# ZIGBEE.net
KiCad netlist of a schematic drawn in Altium Designer
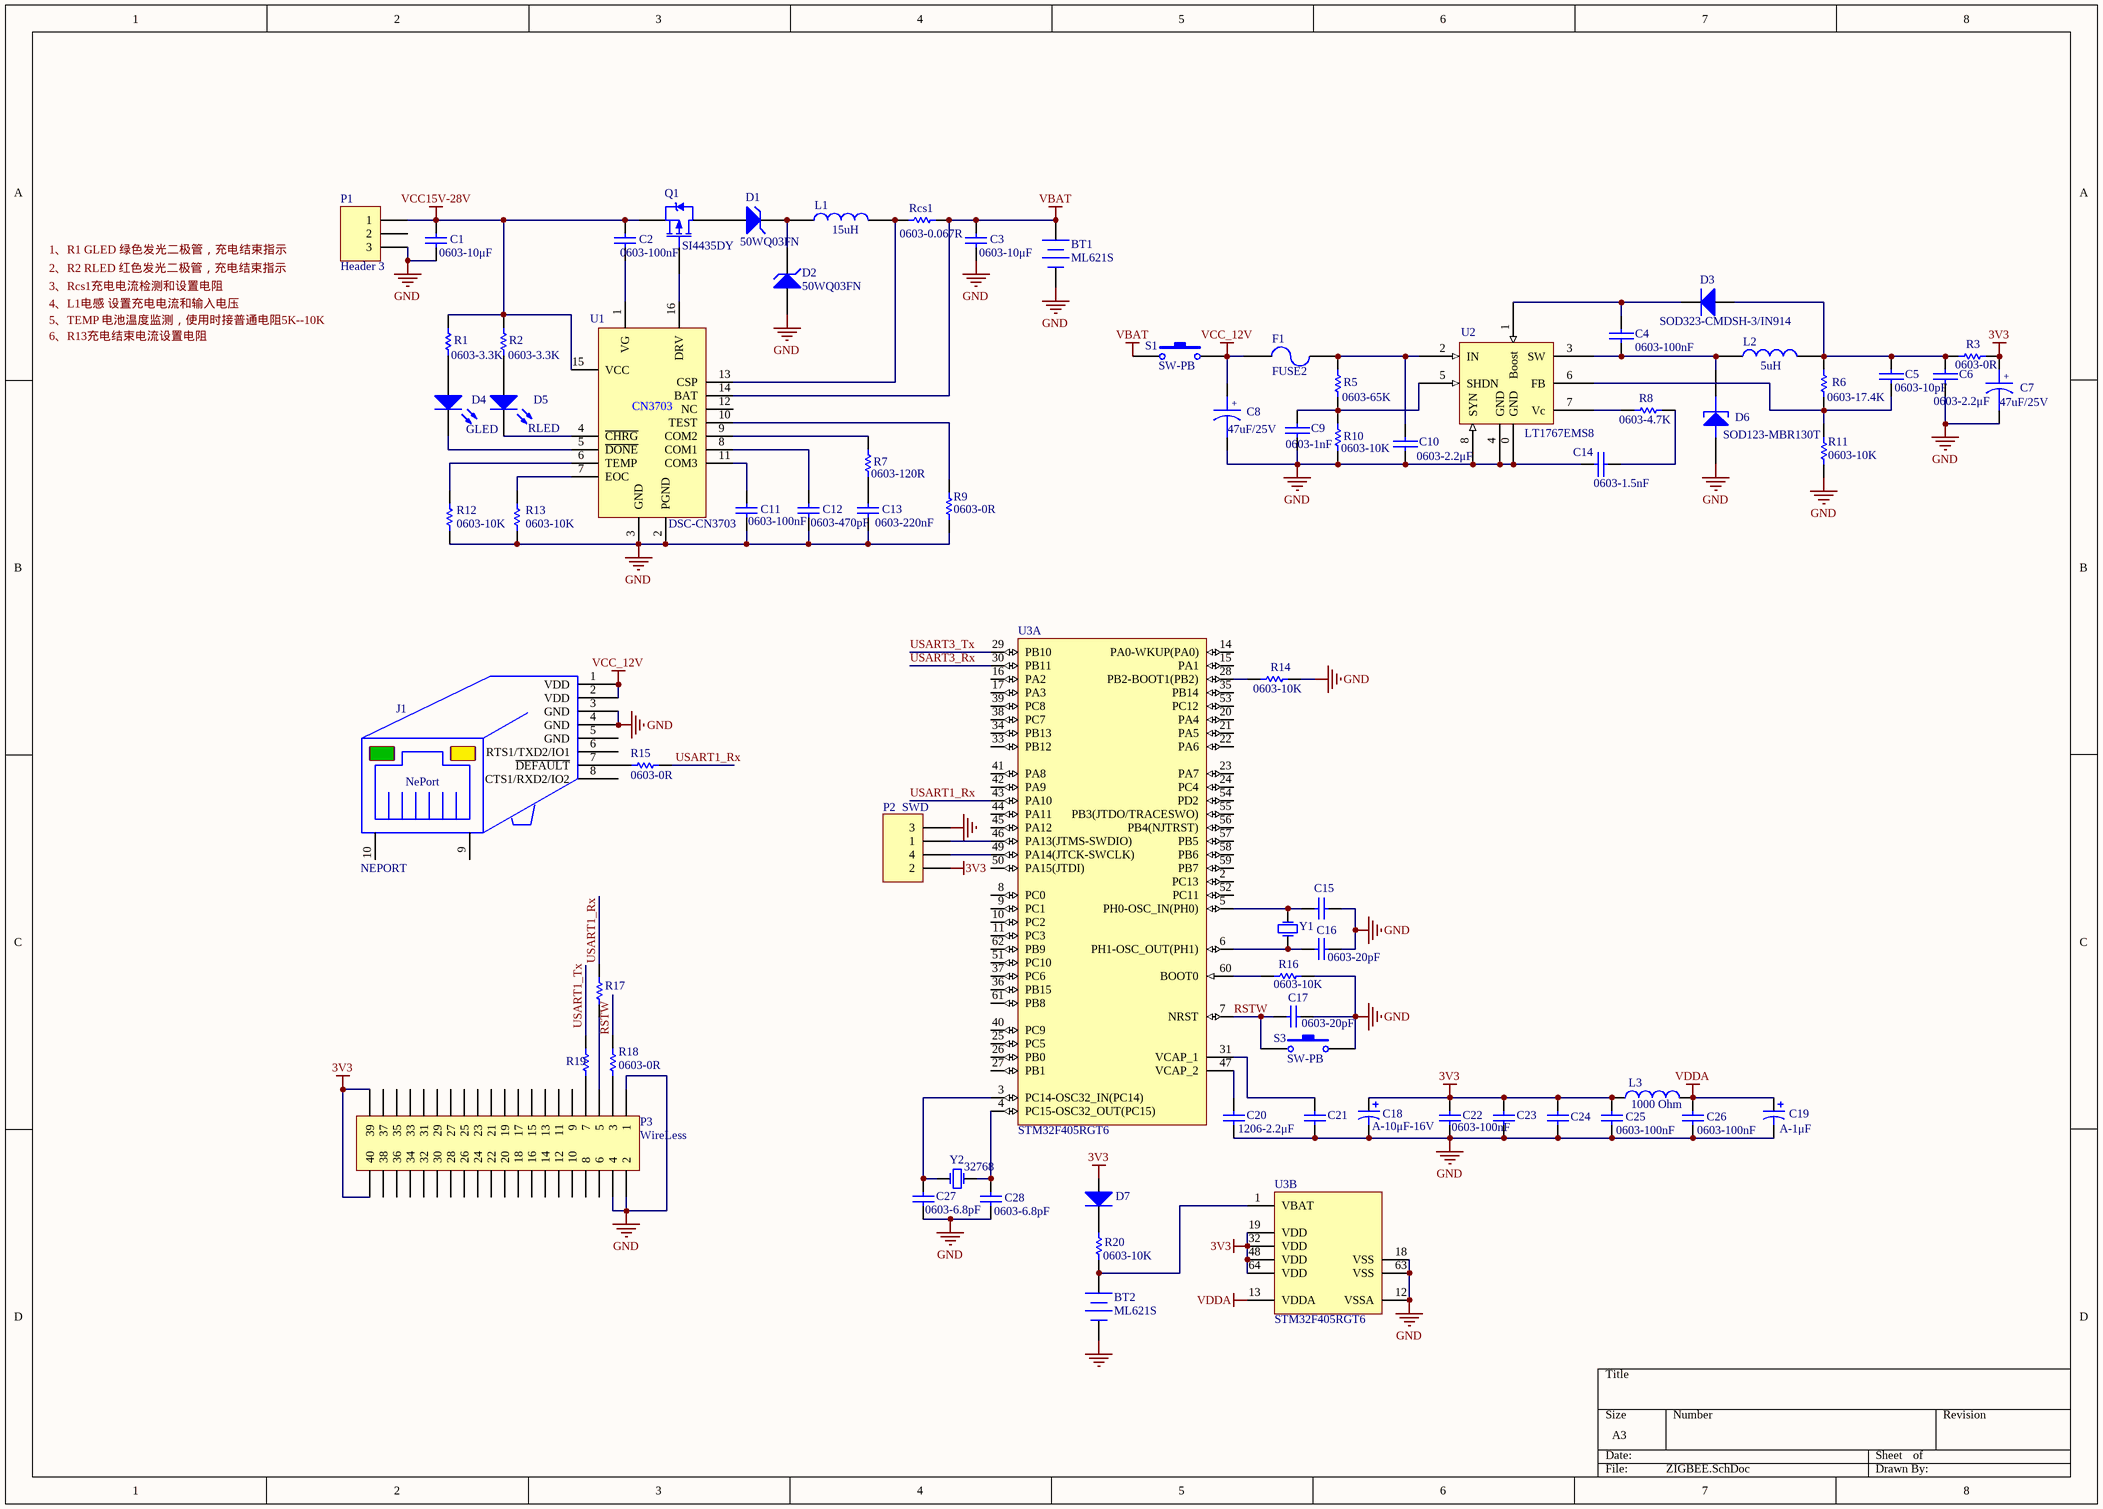
[diagram p0: ZIGBEE.SchDoc]

(export (version "E")
  (design (tool "Eeschema 10.0.6"))
  (components
    (comp (ref "BT1")
      (value "ML621S")
      (footprint "TJC3-2A")
      (description "Multicell Battery")
      (fields (field (name "PUBLISHER") "Altium Limited"))
      (libsource (lib "Miscellaneous Devices") (part "Battery"))
    )
    (comp (ref "BT2")
      (value "ML621S")
      (footprint "ML621")
      (description "Multicell Battery")
      (fields (field (name "PUBLISHER") "Altium Limited"))
      (libsource (lib "Miscellaneous Devices") (part "Battery"))
    )
    (comp (ref "C1")
      (value "0603-10μF")
      (footprint "0603C")
      (description "Capacitor")
      (fields (field (name "PUBLISHER") "Altium Limited"))
      (libsource (lib "Miscellaneous Devices") (part "Cap"))
    )
    (comp (ref "C2")
      (value "0603-100nF")
      (footprint "0603C")
      (description "Capacitor")
      (fields (field (name "PUBLISHER") "Altium Limited"))
      (libsource (lib "Miscellaneous Devices") (part "Cap"))
    )
    (comp (ref "C3")
      (value "0603-10μF")
      (footprint "0603C")
      (description "Capacitor")
      (fields (field (name "PUBLISHER") "Altium Limited"))
      (libsource (lib "Miscellaneous Devices") (part "Cap"))
    )
    (comp (ref "C4")
      (value "0603-100nF")
      (footprint "0603C")
      (description "Capacitor")
      (libsource (lib "采集器") (part "普通电容"))
    )
    (comp (ref "C5")
      (value "0603-10pF")
      (footprint "0603C")
      (description "Capacitor")
      (libsource (lib "采集器") (part "普通电容"))
    )
    (comp (ref "C6")
      (value "0603-2.2μF")
      (footprint "0603C")
      (description "Capacitor")
      (libsource (lib "采集器") (part "普通电容"))
    )
    (comp (ref "C7")
      (value "47uF/25V")
      (footprint "SMD-47uF/25V")
      (description "Capacitor")
      (libsource (lib "采集器") (part "电解电容"))
    )
    (comp (ref "C8")
      (value "47uF/25V")
      (footprint "SMD-47uF/25V")
      (description "Capacitor")
      (libsource (lib "采集器") (part "电解电容"))
    )
    (comp (ref "C9")
      (value "0603-1nF")
      (footprint "0603C")
      (description "Capacitor")
      (libsource (lib "采集器") (part "普通电容"))
    )
    (comp (ref "C10")
      (value "0603-2.2μF")
      (footprint "0603C")
      (description "Capacitor")
      (libsource (lib "采集器") (part "普通电容"))
    )
    (comp (ref "C11")
      (value "0603-100nF")
      (footprint "0603C")
      (description "Capacitor")
      (fields (field (name "PUBLISHER") "Altium Limited"))
      (libsource (lib "Miscellaneous Devices") (part "Cap"))
    )
    (comp (ref "C12")
      (value "0603-470pF")
      (footprint "0603C")
      (description "Capacitor")
      (fields (field (name "PUBLISHER") "Altium Limited"))
      (libsource (lib "Miscellaneous Devices") (part "Cap"))
    )
    (comp (ref "C13")
      (value "0603-220nF")
      (footprint "0603C")
      (description "Capacitor")
      (fields (field (name "PUBLISHER") "Altium Limited"))
      (libsource (lib "Miscellaneous Devices") (part "Cap"))
    )
    (comp (ref "C14")
      (value "0603-1.5nF")
      (footprint "0603C")
      (description "Capacitor")
      (libsource (lib "采集器") (part "普通电容"))
    )
    (comp (ref "C15")
      (value "0603-20pF")
      (footprint "0603C")
      (description "Capacitor")
      (fields (field (name "PUBLISHER") "Altium Limited"))
      (libsource (lib "Miscellaneous Devices") (part "Cap"))
    )
    (comp (ref "C16")
      (value "0603-20pF")
      (footprint "0603C")
      (description "Capacitor")
      (fields (field (name "PUBLISHER") "Altium Limited"))
      (libsource (lib "Miscellaneous Devices") (part "Cap"))
    )
    (comp (ref "C17")
      (value "0603-20pF")
      (footprint "0603C")
      (description "Capacitor")
      (fields (field (name "PUBLISHER") "Altium Limited"))
      (libsource (lib "Miscellaneous Devices") (part "Cap"))
    )
    (comp (ref "C18")
      (value "A-10μF-16V")
      (footprint "TANA")
      (description "Polarized Capacitor (Radial)")
      (fields (field (name "PUBLISHER") "Altium Limited"))
      (libsource (lib "Miscellaneous Devices") (part "Cap Pol1"))
    )
    (comp (ref "C19")
      (value "A-1μF")
      (footprint "TANA")
      (description "Polarized Capacitor (Radial)")
      (fields (field (name "PUBLISHER") "Altium Limited"))
      (libsource (lib "Miscellaneous Devices") (part "Cap Pol1"))
    )
    (comp (ref "C20")
      (value "1206-2.2μF")
      (description "Capacitor")
      (fields (field (name "PUBLISHER") "Altium Limited"))
      (libsource (lib "Miscellaneous Devices") (part "Cap"))
    )
    (comp (ref "C21")
      (value "1206-2.2μF")
      (description "Capacitor")
      (fields (field (name "PUBLISHER") "Altium Limited"))
      (libsource (lib "Miscellaneous Devices") (part "Cap"))
    )
    (comp (ref "C22")
      (value "0603-100nF")
      (footprint "0603C")
      (description "Capacitor")
      (fields (field (name "PUBLISHER") "Altium Limited"))
      (libsource (lib "Miscellaneous Devices") (part "Cap"))
    )
    (comp (ref "C23")
      (value "0603-100nF")
      (footprint "0603C")
      (description "Capacitor")
      (fields (field (name "PUBLISHER") "Altium Limited"))
      (libsource (lib "Miscellaneous Devices") (part "Cap"))
    )
    (comp (ref "C24")
      (value "0603-100nF")
      (footprint "0603C")
      (description "Capacitor")
      (fields (field (name "PUBLISHER") "Altium Limited"))
      (libsource (lib "Miscellaneous Devices") (part "Cap"))
    )
    (comp (ref "C25")
      (value "0603-100nF")
      (footprint "0603C")
      (description "Capacitor")
      (fields (field (name "PUBLISHER") "Altium Limited"))
      (libsource (lib "Miscellaneous Devices") (part "Cap"))
    )
    (comp (ref "C26")
      (value "0603-100nF")
      (footprint "0603C")
      (description "Capacitor")
      (fields (field (name "PUBLISHER") "Altium Limited"))
      (libsource (lib "Miscellaneous Devices") (part "Cap"))
    )
    (comp (ref "C27")
      (value "0603-6.8pF")
      (footprint "0603C")
      (description "Capacitor")
      (fields (field (name "PUBLISHER") "Altium Limited"))
      (libsource (lib "Miscellaneous Devices") (part "Cap"))
    )
    (comp (ref "C28")
      (value "0603-6.8pF")
      (footprint "0603C")
      (description "Capacitor")
      (fields (field (name "PUBLISHER") "Altium Limited"))
      (libsource (lib "Miscellaneous Devices") (part "Cap"))
    )
    (comp (ref "D1")
      (value "50WQ03FN")
      (footprint "DO-214AC")
      (description "Zener Diode")
      (fields (field (name "PUBLISHER") "Altium Limited"))
      (libsource (lib "Miscellaneous Devices") (part "D Zener"))
    )
    (comp (ref "D2")
      (value "50WQ03FN")
      (footprint "DO-214AC")
      (description "Zener Diode")
      (fields (field (name "PUBLISHER") "Altium Limited"))
      (libsource (lib "Miscellaneous Devices") (part "D Zener"))
    )
    (comp (ref "D3")
      (value "SOD323-CMDSH-3/IN914")
      (footprint "SOD-323")
      (libsource (lib "采集器") (part "DIODE"))
    )
    (comp (ref "D4")
      (value "GLED")
      (footprint "0603D")
      (description "Typical INFRARED GaAs LED")
      (fields (field (name "PUBLISHER") "Altium Limited"))
      (libsource (lib "Miscellaneous Devices") (part "LED0"))
    )
    (comp (ref "D5")
      (value "RLED")
      (footprint "0603D")
      (description "Typical INFRARED GaAs LED")
      (fields (field (name "PUBLISHER") "Altium Limited"))
      (libsource (lib "Miscellaneous Devices") (part "LED0"))
    )
    (comp (ref "D6")
      (value "SOD123-MBR130T")
      (footprint "SOD123/X.85")
      (description "Tunnel FDiode")
      (libsource (lib "采集器") (part "TUNNEL"))
    )
    (comp (ref "D7")
      (value "1N4148")
      (footprint "SOD-80/MLL34")
      (description "High Conductance Fast Diode")
      (fields (field (name "PUBLISHER") "Altium Limited"))
      (libsource (lib "Miscellaneous Devices") (part "Diode 1N4148"))
    )
    (comp (ref "F1")
      (value "FUSE2")
      (footprint "0603")
      (description "Fuse")
      (libsource (lib "采集器") (part "FUSE2"))
    )
    (comp (ref "J1")
      (value "NEPORT")
      (footprint "RJ45_8P8C")
      (description "serial to ethernet RJ45 jack")
      (libsource (lib "Neport") (part "NEPORT"))
    )
    (comp (ref "L1") (value "15uH") (footprint "SMD") (libsource (lib "采集器") (part "INDUCTOR")))
    (comp (ref "L2") (value "5uH") (footprint "SMD") (libsource (lib "采集器") (part "INDUCTOR")))
    (comp (ref "L3")
      (value "1000 Ohm")
      (footprint "INDC4516AM")
      (description "BLM41PG102SN1L\\CBW451616U900")
      (fields (field (name "PUBLISHER") "Altium Limited"))
      (libsource (lib "Miscellaneous Devices") (part "Inductor"))
    )
    (comp (ref "P1")
      (value "Header 3")
      (footprint "XH-2.54-3")
      (description "Header, 3-Pin")
      (fields (field (name "PUBLISHER") "Altium Limited"))
      (libsource (lib "Miscellaneous Connectors") (part "Header 3"))
    )
    (comp (ref "P2")
      (value "SWD")
      (footprint "HDR1X4")
      (description "Header, 4-Pin")
      (fields (field (name "PUBLISHER") "Altium Limited"))
      (libsource (lib "Miscellaneous Connectors") (part "Header 4"))
    )
    (comp (ref "P3")
      (value "WireLess")
      (footprint "SMALL/MIDDLE OEM MODEM")
      (description "Header, 20-Pin, Dual row")
      (fields (field (name "PUBLISHER") "Altium Limited"))
      (libsource (lib "Miscellaneous Connectors") (part "Header 20X2"))
    )
    (comp (ref "Q1")
      (value "SI4435DY")
      (footprint "TO-220AB")
      (description "P-Channel Power MOSFET")
      (fields (field (name "PUBLISHER") "Altium Limited"))
      (libsource (lib "Miscellaneous Devices") (part "PMOS-2"))
    )
    (comp (ref "R1")
      (value "0603-3.3K")
      (footprint "0603")
      (description "Resistor")
      (fields (field (name "PUBLISHER") "Altium Limited"))
      (libsource (lib "Miscellaneous Devices") (part "Res1"))
    )
    (comp (ref "R2")
      (value "0603-3.3K")
      (footprint "0603")
      (description "Resistor")
      (fields (field (name "PUBLISHER") "Altium Limited"))
      (libsource (lib "Miscellaneous Devices") (part "Res1"))
    )
    (comp (ref "R3")
      (value "0603-0R")
      (footprint "0603")
      (description "Resistor")
      (fields (field (name "PUBLISHER") "Altium Limited"))
      (libsource (lib "Miscellaneous Devices") (part "Res1"))
    )
    (comp (ref "R5")
      (value "0603-65K")
      (footprint "0603")
      (description "Resistor")
      (fields (field (name "PUBLISHER") "Altium Limited"))
      (libsource (lib "Miscellaneous Devices") (part "Res1"))
    )
    (comp (ref "R6")
      (value "0603-17.4K")
      (footprint "0603")
      (description "Resistor")
      (fields (field (name "PUBLISHER") "Altium Limited"))
      (libsource (lib "Miscellaneous Devices") (part "Res1"))
    )
    (comp (ref "R7")
      (value "0603-120R")
      (footprint "0603")
      (description "Resistor")
      (fields (field (name "PUBLISHER") "Altium Limited"))
      (libsource (lib "Miscellaneous Devices") (part "Res1"))
    )
    (comp (ref "R8")
      (value "0603-4.7K")
      (footprint "0603")
      (description "Resistor")
      (fields (field (name "PUBLISHER") "Altium Limited"))
      (libsource (lib "Miscellaneous Devices") (part "Res1"))
    )
    (comp (ref "R9")
      (value "0603-0R")
      (footprint "0603")
      (description "Resistor")
      (fields (field (name "PUBLISHER") "Altium Limited"))
      (libsource (lib "Miscellaneous Devices") (part "Res1"))
    )
    (comp (ref "R10")
      (value "0603-10K")
      (footprint "0603")
      (description "Resistor")
      (fields (field (name "PUBLISHER") "Altium Limited"))
      (libsource (lib "Miscellaneous Devices") (part "Res1"))
    )
    (comp (ref "R11")
      (value "0603-10K")
      (footprint "0603")
      (description "Resistor")
      (fields (field (name "PUBLISHER") "Altium Limited"))
      (libsource (lib "Miscellaneous Devices") (part "Res1"))
    )
    (comp (ref "R12")
      (value "0603-10K")
      (footprint "0603")
      (description "Resistor")
      (fields (field (name "PUBLISHER") "Altium Limited"))
      (libsource (lib "Miscellaneous Devices") (part "Res1"))
    )
    (comp (ref "R13")
      (value "0603-10K")
      (footprint "0603")
      (description "Resistor")
      (fields (field (name "PUBLISHER") "Altium Limited"))
      (libsource (lib "Miscellaneous Devices") (part "Res1"))
    )
    (comp (ref "R14")
      (value "0603-10K")
      (footprint "0603")
      (description "Resistor")
      (fields (field (name "PUBLISHER") "Altium Limited"))
      (libsource (lib "Miscellaneous Devices") (part "Res1"))
    )
    (comp (ref "R15")
      (value "0603-0R")
      (footprint "0603")
      (description "Resistor")
      (fields (field (name "PUBLISHER") "Altium Limited"))
      (libsource (lib "Miscellaneous Devices") (part "Res1"))
    )
    (comp (ref "R16")
      (value "0603-10K")
      (footprint "0603")
      (description "Resistor")
      (fields (field (name "PUBLISHER") "Altium Limited"))
      (libsource (lib "Miscellaneous Devices") (part "Res1"))
    )
    (comp (ref "R17")
      (value "0603-0R")
      (footprint "0603")
      (description "Resistor")
      (fields (field (name "PUBLISHER") "Altium Limited"))
      (libsource (lib "Miscellaneous Devices") (part "Res1"))
    )
    (comp (ref "R18")
      (value "0603-0R")
      (footprint "0603")
      (description "Resistor")
      (fields (field (name "PUBLISHER") "Altium Limited"))
      (libsource (lib "Miscellaneous Devices") (part "Res1"))
    )
    (comp (ref "R19")
      (value "0603-0R")
      (footprint "0603")
      (description "Resistor")
      (fields (field (name "PUBLISHER") "Altium Limited"))
      (libsource (lib "Miscellaneous Devices") (part "Res1"))
    )
    (comp (ref "R20")
      (value "0603-10K")
      (footprint "0603")
      (description "Resistor")
      (fields (field (name "PUBLISHER") "Altium Limited"))
      (libsource (lib "Miscellaneous Devices") (part "Res1"))
    )
    (comp (ref "Rcs1")
      (value "0603-0.067R")
      (footprint "0603")
      (description "Resistor")
      (fields (field (name "PUBLISHER") "Altium Limited"))
      (libsource (lib "Miscellaneous Devices") (part "Res1"))
    )
    (comp (ref "S1")
      (value "SW-PB")
      (footprint "TJC3-2A")
      (description "Switch")
      (fields (field (name "PUBLISHER") "Altium Limited"))
      (libsource (lib "Miscellaneous Devices") (part "SW-PB"))
    )
    (comp (ref "S3")
      (value "SW-PB")
      (footprint "SW3*4*2MM")
      (description "Switch")
      (fields (field (name "PUBLISHER") "Altium Limited"))
      (libsource (lib "Miscellaneous Devices") (part "SW-PB"))
    )
    (comp (ref "U1") (value "DSC-CN3703") (footprint "TSSOP16") (libsource (lib "SCHKU") (part "DSC-CN3703")))
    (comp (ref "U2") (value "LT1767EMS8") (footprint "MS8_N") (libsource (lib "采集器") (part "LT1767EMS8")))
    (comp (ref "U3")
      (value "STM32F405RGT6")
      (footprint "TQFP64_M")
      (fields (field (name "MANUFACTURER") "STMicroelectronics"))
      (libsource (lib "") (part "STM32F405RGT6_1"))
    )
    (comp (ref "Y1")
      (value "8MHz")
      (footprint "XTAL")
      (description "Crystal Oscillator")
      (fields (field (name "PUBLISHER") "Altium Limited"))
      (libsource (lib "Miscellaneous Devices") (part "XTAL"))
    )
    (comp (ref "Y2")
      (value "32768")
      (footprint "1206CY")
      (description "Crystal Oscillator")
      (fields (field (name "PUBLISHER") "Altium Limited"))
      (libsource (lib "Miscellaneous Devices") (part "XTAL"))
    )
  )
  (nets
    (net (code "7") (name "/RSTW") (class "Default")
      (node (ref "C17") (pin "2") (pinfunction "2_2") (pintype "passive"))
      (node (ref "R18") (pin "1") (pinfunction "1_1") (pintype "passive"))
      (node (ref "S3") (pin "1") (pinfunction "1_1") (pintype "passive"))
      (node (ref "U3") (pin "7") (pinfunction "NRST_7") (pintype "bidirectional"))
    )
    (net (code "8") (name "/USART1_Rx") (class "Default")
      (node (ref "R15") (pin "1") (pinfunction "1_1") (pintype "passive"))
      (node (ref "R17") (pin "1") (pinfunction "1_1") (pintype "passive"))
      (node (ref "U3") (pin "43") (pinfunction "PA10_43") (pintype "bidirectional"))
    )
    (net (code "9") (name "/USART1_Tx") (class "Default")
      (node (ref "R19") (pin "1") (pinfunction "1_1") (pintype "passive"))
    )
    (net (code "10") (name "/USART3_Rx") (class "Default")
      (node (ref "U3") (pin "30") (pinfunction "PB11_30") (pintype "bidirectional"))
    )
    (net (code "11") (name "/USART3_Tx") (class "Default")
      (node (ref "U3") (pin "29") (pinfunction "PB10_29") (pintype "bidirectional"))
    )
    (net (code "12") (name "3V3") (class "Default")
      (node (ref "C18") (pin "1") (pinfunction "1_1") (pintype "passive"))
      (node (ref "C22") (pin "2") (pinfunction "2_2") (pintype "passive"))
      (node (ref "C23") (pin "2") (pinfunction "2_2") (pintype "passive"))
      (node (ref "C24") (pin "2") (pinfunction "2_2") (pintype "passive"))
      (node (ref "C25") (pin "2") (pinfunction "2_2") (pintype "passive"))
      (node (ref "C7") (pin "1") (pinfunction "1_1") (pintype "passive"))
      (node (ref "D7") (pin "1") (pinfunction "A_1") (pintype "passive"))
      (node (ref "L3") (pin "1") (pinfunction "1_1") (pintype "passive"))
      (node (ref "P2") (pin "2") (pinfunction "2_2") (pintype "passive"))
      (node (ref "P3") (pin "39") (pinfunction "39_39") (pintype "passive"))
      (node (ref "P3") (pin "40") (pinfunction "40_40") (pintype "passive"))
      (node (ref "R3") (pin "2") (pinfunction "2_2") (pintype "passive"))
      (node (ref "U3") (pin "19") (pinfunction "VDD_19") (pintype "power_in"))
      (node (ref "U3") (pin "32") (pinfunction "VDD_32") (pintype "power_in"))
      (node (ref "U3") (pin "48") (pinfunction "VDD_48") (pintype "power_in"))
      (node (ref "U3") (pin "64") (pinfunction "VDD_64") (pintype "power_in"))
    )
    (net (code "13") (name "GND") (class "Default")
      (node (ref "BT1") (pin "1") (pinfunction "-_1") (pintype "passive"))
      (node (ref "BT2") (pin "1") (pinfunction "-_1") (pintype "passive"))
      (node (ref "C1") (pin "2") (pinfunction "2_2") (pintype "passive"))
      (node (ref "C10") (pin "2") (pinfunction "2_2") (pintype "passive"))
      (node (ref "C11") (pin "2") (pinfunction "2_2") (pintype "passive"))
      (node (ref "C12") (pin "2") (pinfunction "2_2") (pintype "passive"))
      (node (ref "C13") (pin "2") (pinfunction "2_2") (pintype "passive"))
      (node (ref "C14") (pin "1") (pinfunction "1_1") (pintype "passive"))
      (node (ref "C15") (pin "1") (pinfunction "1_1") (pintype "passive"))
      (node (ref "C16") (pin "1") (pinfunction "1_1") (pintype "passive"))
      (node (ref "C17") (pin "1") (pinfunction "1_1") (pintype "passive"))
      (node (ref "C18") (pin "2") (pinfunction "2_2") (pintype "passive"))
      (node (ref "C19") (pin "2") (pinfunction "2_2") (pintype "passive"))
      (node (ref "C20") (pin "1") (pinfunction "1_1") (pintype "passive"))
      (node (ref "C21") (pin "1") (pinfunction "1_1") (pintype "passive"))
      (node (ref "C22") (pin "1") (pinfunction "1_1") (pintype "passive"))
      (node (ref "C23") (pin "1") (pinfunction "1_1") (pintype "passive"))
      (node (ref "C24") (pin "1") (pinfunction "1_1") (pintype "passive"))
      (node (ref "C25") (pin "1") (pinfunction "1_1") (pintype "passive"))
      (node (ref "C26") (pin "1") (pinfunction "1_1") (pintype "passive"))
      (node (ref "C27") (pin "2") (pinfunction "2_2") (pintype "passive"))
      (node (ref "C28") (pin "2") (pinfunction "2_2") (pintype "passive"))
      (node (ref "C3") (pin "2") (pinfunction "2_2") (pintype "passive"))
      (node (ref "C6") (pin "2") (pinfunction "2_2") (pintype "passive"))
      (node (ref "C7") (pin "2") (pinfunction "2_2") (pintype "passive"))
      (node (ref "C8") (pin "2") (pinfunction "2_2") (pintype "passive"))
      (node (ref "C9") (pin "2") (pinfunction "2_2") (pintype "passive"))
      (node (ref "D2") (pin "1") (pinfunction "A_1") (pintype "passive"))
      (node (ref "D6") (pin "1") (pinfunction "A_1") (pintype "passive"))
      (node (ref "J1") (pin "3") (pinfunction "GND_3") (pintype "passive"))
      (node (ref "J1") (pin "4") (pinfunction "GND_4") (pintype "passive"))
      (node (ref "P1") (pin "3") (pinfunction "3_3") (pintype "passive"))
      (node (ref "P2") (pin "3") (pinfunction "3_3") (pintype "passive"))
      (node (ref "P3") (pin "1") (pinfunction "1_1") (pintype "passive"))
      (node (ref "P3") (pin "2") (pinfunction "2_2") (pintype "passive"))
      (node (ref "P3") (pin "4") (pinfunction "4_4") (pintype "passive"))
      (node (ref "R10") (pin "1") (pinfunction "1_1") (pintype "passive"))
      (node (ref "R11") (pin "1") (pinfunction "1_1") (pintype "passive"))
      (node (ref "R12") (pin "2") (pinfunction "2_2") (pintype "passive"))
      (node (ref "R13") (pin "2") (pinfunction "2_2") (pintype "passive"))
      (node (ref "R14") (pin "2") (pinfunction "2_2") (pintype "passive"))
      (node (ref "R16") (pin "2") (pinfunction "2_2") (pintype "passive"))
      (node (ref "R9") (pin "2") (pinfunction "2_2") (pintype "passive"))
      (node (ref "S3") (pin "2") (pinfunction "2_2") (pintype "passive"))
      (node (ref "U1") (pin "2") (pinfunction "PGND_2") (pintype "passive"))
      (node (ref "U1") (pin "3") (pinfunction "GND_3") (pintype "passive"))
      (node (ref "U2") (pin "0") (pinfunction "GND_0") (pintype "passive"))
      (node (ref "U2") (pin "4") (pinfunction "GND_4") (pintype "passive"))
      (node (ref "U2") (pin "8") (pinfunction "SYN_8") (pintype "input"))
      (node (ref "U3") (pin "12") (pinfunction "VSSA_12") (pintype "power_in"))
      (node (ref "U3") (pin "18") (pinfunction "VSS_18") (pintype "power_in"))
      (node (ref "U3") (pin "63") (pinfunction "VSS_63") (pintype "power_in"))
    )
    (net (code "14") (name "Net-(BT2-+)") (class "Default")
      (node (ref "BT2") (pin "2") (pinfunction "+_2") (pintype "passive"))
      (node (ref "R20") (pin "2") (pinfunction "2_2") (pintype "passive"))
      (node (ref "U3") (pin "1") (pinfunction "VBAT_1") (pintype "power_in"))
    )
    (net (code "15") (name "Net-(C13-Pad1)") (class "Default")
      (node (ref "C13") (pin "1") (pinfunction "1_1") (pintype "passive"))
      (node (ref "R7") (pin "2") (pinfunction "2_2") (pintype "passive"))
    )
    (net (code "16") (name "Net-(C14-Pad2)") (class "Default")
      (node (ref "C14") (pin "2") (pinfunction "2_2") (pintype "passive"))
      (node (ref "R8") (pin "1") (pinfunction "1_1") (pintype "passive"))
    )
    (net (code "17") (name "Net-(D1-A)") (class "Default")
      (node (ref "D1") (pin "1") (pinfunction "A_1") (pintype "passive"))
      (node (ref "Q1") (pin "2") (pinfunction "D_2") (pintype "passive"))
    )
    (net (code "18") (name "Net-(D1-K)") (class "Default")
      (node (ref "D1") (pin "2") (pinfunction "K_2") (pintype "passive"))
      (node (ref "D2") (pin "2") (pinfunction "K_2") (pintype "passive"))
      (node (ref "L1") (pin "1") (pinfunction "1_1") (pintype "passive"))
    )
    (net (code "19") (name "Net-(D3-A)") (class "Default")
      (node (ref "C5") (pin "1") (pinfunction "1_1") (pintype "passive"))
      (node (ref "C6") (pin "1") (pinfunction "1_1") (pintype "passive"))
      (node (ref "D3") (pin "1") (pinfunction "A_1") (pintype "passive"))
      (node (ref "L2") (pin "2") (pinfunction "2_2") (pintype "passive"))
      (node (ref "R3") (pin "1") (pinfunction "1_1") (pintype "passive"))
      (node (ref "R6") (pin "2") (pinfunction "2_2") (pintype "passive"))
    )
    (net (code "20") (name "Net-(D3-K)") (class "Default")
      (node (ref "C4") (pin "1") (pinfunction "1_1") (pintype "passive"))
      (node (ref "D3") (pin "2") (pinfunction "K_2") (pintype "passive"))
      (node (ref "U2") (pin "1") (pinfunction "Boost_1") (pintype "input"))
    )
    (net (code "21") (name "Net-(D4-A)") (class "Default")
      (node (ref "D4") (pin "1") (pinfunction "A_1") (pintype "passive"))
      (node (ref "R1") (pin "1") (pinfunction "1_1") (pintype "passive"))
    )
    (net (code "22") (name "Net-(D4-K)") (class "Default")
      (node (ref "D4") (pin "2") (pinfunction "K_2") (pintype "passive"))
      (node (ref "U1") (pin "5") (pinfunction "~{DONE}_5") (pintype "passive"))
    )
    (net (code "23") (name "Net-(D5-A)") (class "Default")
      (node (ref "D5") (pin "1") (pinfunction "A_1") (pintype "passive"))
      (node (ref "R2") (pin "1") (pinfunction "1_1") (pintype "passive"))
    )
    (net (code "24") (name "Net-(D5-K)") (class "Default")
      (node (ref "D5") (pin "2") (pinfunction "K_2") (pintype "passive"))
      (node (ref "U1") (pin "4") (pinfunction "~{CHRG}_4") (pintype "passive"))
    )
    (net (code "25") (name "Net-(D6-K)") (class "Default")
      (node (ref "C4") (pin "2") (pinfunction "2_2") (pintype "passive"))
      (node (ref "D6") (pin "2") (pinfunction "K_2") (pintype "passive"))
      (node (ref "L2") (pin "1") (pinfunction "1_1") (pintype "passive"))
      (node (ref "U2") (pin "3") (pinfunction "SW_3") (pintype "passive"))
    )
    (net (code "26") (name "Net-(D7-K)") (class "Default")
      (node (ref "D7") (pin "2") (pinfunction "K_2") (pintype "passive"))
      (node (ref "R20") (pin "1") (pinfunction "1_1") (pintype "passive"))
    )
    (net (code "27") (name "Net-(J1-~{DEFAULT})") (class "Default")
      (node (ref "J1") (pin "7") (pinfunction "~{DEFAULT}_7") (pintype "passive"))
      (node (ref "R15") (pin "2") (pinfunction "2_2") (pintype "passive"))
    )
    (net (code "28") (name "Net-(P3-Pad3)") (class "Default")
      (node (ref "P3") (pin "3") (pinfunction "3_3") (pintype "passive"))
      (node (ref "R18") (pin "2") (pinfunction "2_2") (pintype "passive"))
    )
    (net (code "29") (name "Net-(P3-Pad5)") (class "Default")
      (node (ref "P3") (pin "5") (pinfunction "5_5") (pintype "passive"))
      (node (ref "R17") (pin "2") (pinfunction "2_2") (pintype "passive"))
    )
    (net (code "30") (name "Net-(P3-Pad7)") (class "Default")
      (node (ref "P3") (pin "7") (pinfunction "7_7") (pintype "passive"))
      (node (ref "R19") (pin "2") (pinfunction "2_2") (pintype "passive"))
    )
    (net (code "31") (name "Net-(Q1-G)") (class "Default")
      (node (ref "Q1") (pin "1") (pinfunction "G_1") (pintype "passive"))
      (node (ref "U1") (pin "16") (pinfunction "DRV_16") (pintype "passive"))
    )
    (net (code "32") (name "Net-(U1-COM1)") (class "Default")
      (node (ref "C12") (pin "1") (pinfunction "1_1") (pintype "passive"))
      (node (ref "U1") (pin "8") (pinfunction "COM1_8") (pintype "passive"))
    )
    (net (code "33") (name "Net-(U1-COM2)") (class "Default")
      (node (ref "R7") (pin "1") (pinfunction "1_1") (pintype "passive"))
      (node (ref "U1") (pin "9") (pinfunction "COM2_9") (pintype "passive"))
    )
    (net (code "34") (name "Net-(U1-COM3)") (class "Default")
      (node (ref "C11") (pin "1") (pinfunction "1_1") (pintype "passive"))
      (node (ref "U1") (pin "11") (pinfunction "COM3_11") (pintype "passive"))
    )
    (net (code "35") (name "Net-(U1-CSP)") (class "Default")
      (node (ref "L1") (pin "2") (pinfunction "2_2") (pintype "passive"))
      (node (ref "Rcs1") (pin "2") (pinfunction "2_2") (pintype "passive"))
      (node (ref "U1") (pin "13") (pinfunction "CSP_13") (pintype "passive"))
    )
    (net (code "36") (name "Net-(U1-EOC)") (class "Default")
      (node (ref "R13") (pin "1") (pinfunction "1_1") (pintype "passive"))
      (node (ref "U1") (pin "7") (pinfunction "EOC_7") (pintype "passive"))
    )
    (net (code "37") (name "Net-(U1-TEMP)") (class "Default")
      (node (ref "R12") (pin "1") (pinfunction "1_1") (pintype "passive"))
      (node (ref "U1") (pin "6") (pinfunction "TEMP_6") (pintype "passive"))
    )
    (net (code "38") (name "Net-(U1-TEST)") (class "Default")
      (node (ref "R9") (pin "1") (pinfunction "1_1") (pintype "passive"))
      (node (ref "U1") (pin "10") (pinfunction "TEST_10") (pintype "passive"))
    )
    (net (code "39") (name "Net-(U1-VG)") (class "Default")
      (node (ref "C2") (pin "2") (pinfunction "2_2") (pintype "passive"))
      (node (ref "U1") (pin "1") (pinfunction "VG_1") (pintype "passive"))
    )
    (net (code "40") (name "Net-(U2-FB)") (class "Default")
      (node (ref "C5") (pin "2") (pinfunction "2_2") (pintype "passive"))
      (node (ref "R11") (pin "2") (pinfunction "2_2") (pintype "passive"))
      (node (ref "R6") (pin "1") (pinfunction "1_1") (pintype "passive"))
      (node (ref "U2") (pin "6") (pinfunction "FB_6") (pintype "passive"))
    )
    (net (code "41") (name "Net-(U2-IN)") (class "Default")
      (node (ref "C10") (pin "1") (pinfunction "1_1") (pintype "passive"))
      (node (ref "F1") (pin "2") (pinfunction "2_2") (pintype "passive"))
      (node (ref "R5") (pin "2") (pinfunction "2_2") (pintype "passive"))
      (node (ref "U2") (pin "2") (pinfunction "IN_2") (pintype "input"))
    )
    (net (code "42") (name "Net-(U2-SHDN)") (class "Default")
      (node (ref "C9") (pin "1") (pinfunction "1_1") (pintype "passive"))
      (node (ref "R10") (pin "2") (pinfunction "2_2") (pintype "passive"))
      (node (ref "R5") (pin "1") (pinfunction "1_1") (pintype "passive"))
      (node (ref "U2") (pin "5") (pinfunction "SHDN_5") (pintype "input"))
    )
    (net (code "43") (name "Net-(U2-Vc)") (class "Default")
      (node (ref "R8") (pin "2") (pinfunction "2_2") (pintype "passive"))
      (node (ref "U2") (pin "7") (pinfunction "Vc_7") (pintype "passive"))
    )
    (net (code "44") (name "Net-(U3A-BOOT0)") (class "Default")
      (node (ref "R16") (pin "1") (pinfunction "1_1") (pintype "passive"))
      (node (ref "U3") (pin "60") (pinfunction "BOOT0_60") (pintype "input"))
    )
    (net (code "45") (name "Net-(U3A-PA13(JTMS-SWDIO))") (class "Default")
      (node (ref "P2") (pin "1") (pinfunction "1_1") (pintype "passive"))
      (node (ref "U3") (pin "46") (pinfunction "PA13(JTMS-SWDIO)_46") (pintype "bidirectional"))
    )
    (net (code "46") (name "Net-(U3A-PA14(JTCK-SWCLK))") (class "Default")
      (node (ref "P2") (pin "4") (pinfunction "4_4") (pintype "passive"))
      (node (ref "U3") (pin "49") (pinfunction "PA14(JTCK-SWCLK)_49") (pintype "bidirectional"))
    )
    (net (code "47") (name "Net-(U3A-PB2-BOOT1(PB2))") (class "Default")
      (node (ref "R14") (pin "1") (pinfunction "1_1") (pintype "passive"))
      (node (ref "U3") (pin "28") (pinfunction "PB2-BOOT1(PB2)_28") (pintype "bidirectional"))
    )
    (net (code "48") (name "Net-(U3A-PC14-OSC32_IN(PC14))") (class "Default")
      (node (ref "C27") (pin "1") (pinfunction "1_1") (pintype "passive"))
      (node (ref "U3") (pin "3") (pinfunction "PC14-OSC32_IN(PC14)_3") (pintype "bidirectional"))
      (node (ref "Y2") (pin "2") (pinfunction "OSC2_2") (pintype "passive"))
    )
    (net (code "49") (name "Net-(U3A-PC15-OSC32_OUT(PC15))") (class "Default")
      (node (ref "C28") (pin "1") (pinfunction "1_1") (pintype "passive"))
      (node (ref "U3") (pin "4") (pinfunction "PC15-OSC32_OUT(PC15)_4") (pintype "bidirectional"))
      (node (ref "Y2") (pin "1") (pinfunction "OSC1_1") (pintype "passive"))
    )
    (net (code "50") (name "Net-(U3A-PH0-OSC_IN(PH0))") (class "Default")
      (node (ref "C15") (pin "2") (pinfunction "2_2") (pintype "passive"))
      (node (ref "U3") (pin "5") (pinfunction "PH0-OSC_IN(PH0)_5") (pintype "bidirectional"))
      (node (ref "Y1") (pin "2") (pinfunction "OSC2_2") (pintype "passive"))
    )
    (net (code "51") (name "Net-(U3A-PH1-OSC_OUT(PH1))") (class "Default")
      (node (ref "C16") (pin "2") (pinfunction "2_2") (pintype "passive"))
      (node (ref "U3") (pin "6") (pinfunction "PH1-OSC_OUT(PH1)_6") (pintype "bidirectional"))
      (node (ref "Y1") (pin "1") (pinfunction "OSC1_1") (pintype "passive"))
    )
    (net (code "52") (name "Net-(U3A-VCAP_1)") (class "Default")
      (node (ref "C21") (pin "2") (pinfunction "2_2") (pintype "passive"))
      (node (ref "U3") (pin "31") (pinfunction "VCAP_1_31") (pintype "power_in"))
    )
    (net (code "53") (name "Net-(U3A-VCAP_2)") (class "Default")
      (node (ref "C20") (pin "2") (pinfunction "2_2") (pintype "passive"))
      (node (ref "U3") (pin "47") (pinfunction "VCAP_2_47") (pintype "power_in"))
    )
    (net (code "54") (name "VBAT") (class "Default")
      (node (ref "BT1") (pin "2") (pinfunction "+_2") (pintype "passive"))
      (node (ref "C3") (pin "1") (pinfunction "1_1") (pintype "passive"))
      (node (ref "Rcs1") (pin "1") (pinfunction "1_1") (pintype "passive"))
      (node (ref "S1") (pin "1") (pinfunction "1_1") (pintype "passive"))
      (node (ref "U1") (pin "14") (pinfunction "BAT_14") (pintype "passive"))
    )
    (net (code "55") (name "VCC15V-28V") (class "Default")
      (node (ref "C1") (pin "1") (pinfunction "1_1") (pintype "passive"))
      (node (ref "C2") (pin "1") (pinfunction "1_1") (pintype "passive"))
      (node (ref "P1") (pin "1") (pinfunction "1_1") (pintype "passive"))
      (node (ref "Q1") (pin "3") (pinfunction "S_3") (pintype "passive"))
      (node (ref "R1") (pin "2") (pinfunction "2_2") (pintype "passive"))
      (node (ref "R2") (pin "2") (pinfunction "2_2") (pintype "passive"))
      (node (ref "U1") (pin "15") (pinfunction "VCC_15") (pintype "passive"))
    )
    (net (code "56") (name "VCC_12V") (class "Default")
      (node (ref "C8") (pin "1") (pinfunction "1_1") (pintype "passive"))
      (node (ref "F1") (pin "1") (pinfunction "1_1") (pintype "passive"))
      (node (ref "J1") (pin "1") (pinfunction "VDD_1") (pintype "passive"))
      (node (ref "J1") (pin "2") (pinfunction "VDD_2") (pintype "passive"))
      (node (ref "S1") (pin "2") (pinfunction "2_2") (pintype "passive"))
    )
    (net (code "57") (name "VDDA") (class "Default")
      (node (ref "C19") (pin "1") (pinfunction "1_1") (pintype "passive"))
      (node (ref "C26") (pin "2") (pinfunction "2_2") (pintype "passive"))
      (node (ref "L3") (pin "2") (pinfunction "2_2") (pintype "passive"))
      (node (ref "U3") (pin "13") (pinfunction "VDDA_13") (pintype "power_in"))
    )
    (net (code "58") (name "unconnected-(J1-CTS1{slash}RXD2{slash}IO2-Pad8)") (class "Default")
      (node (ref "J1") (pin "8") (pinfunction "CTS1/RXD2/IO2_8") (pintype "passive"))
    )
    (net (code "59") (name "unconnected-(J1-GND-Pad5)") (class "Default")
      (node (ref "J1") (pin "5") (pinfunction "GND_5") (pintype "passive"))
    )
    (net (code "60") (name "unconnected-(J1-RTS1{slash}TXD2{slash}IO1-Pad6)") (class "Default")
      (node (ref "J1") (pin "6") (pinfunction "RTS1/TXD2/IO1_6") (pintype "passive"))
    )
    (net (code "61") (name "unconnected-(J1-SHELL-Pad9)") (class "Default")
      (node (ref "J1") (pin "9") (pinfunction "SHELL_9") (pintype "passive"))
    )
    (net (code "62") (name "unconnected-(J1-SHELL-Pad10)") (class "Default")
      (node (ref "J1") (pin "10") (pinfunction "SHELL_10") (pintype "passive"))
    )
    (net (code "63") (name "unconnected-(P1-Pad2)") (class "Default")
      (node (ref "P1") (pin "2") (pinfunction "2_2") (pintype "passive"))
    )
    (net (code "64") (name "unconnected-(P3-Pad6)") (class "Default")
      (node (ref "P3") (pin "6") (pinfunction "6_6") (pintype "passive"))
    )
    (net (code "65") (name "unconnected-(P3-Pad8)") (class "Default")
      (node (ref "P3") (pin "8") (pinfunction "8_8") (pintype "passive"))
    )
    (net (code "66") (name "unconnected-(P3-Pad9)") (class "Default")
      (node (ref "P3") (pin "9") (pinfunction "9_9") (pintype "passive"))
    )
    (net (code "67") (name "unconnected-(P3-Pad10)") (class "Default")
      (node (ref "P3") (pin "10") (pinfunction "10_10") (pintype "passive"))
    )
    (net (code "68") (name "unconnected-(P3-Pad11)") (class "Default")
      (node (ref "P3") (pin "11") (pinfunction "11_11") (pintype "passive"))
    )
    (net (code "69") (name "unconnected-(P3-Pad12)") (class "Default")
      (node (ref "P3") (pin "12") (pinfunction "12_12") (pintype "passive"))
    )
    (net (code "70") (name "unconnected-(P3-Pad13)") (class "Default")
      (node (ref "P3") (pin "13") (pinfunction "13_13") (pintype "passive"))
    )
    (net (code "71") (name "unconnected-(P3-Pad14)") (class "Default")
      (node (ref "P3") (pin "14") (pinfunction "14_14") (pintype "passive"))
    )
    (net (code "72") (name "unconnected-(P3-Pad15)") (class "Default")
      (node (ref "P3") (pin "15") (pinfunction "15_15") (pintype "passive"))
    )
    (net (code "73") (name "unconnected-(P3-Pad16)") (class "Default")
      (node (ref "P3") (pin "16") (pinfunction "16_16") (pintype "passive"))
    )
    (net (code "74") (name "unconnected-(P3-Pad17)") (class "Default")
      (node (ref "P3") (pin "17") (pinfunction "17_17") (pintype "passive"))
    )
    (net (code "75") (name "unconnected-(P3-Pad18)") (class "Default")
      (node (ref "P3") (pin "18") (pinfunction "18_18") (pintype "passive"))
    )
    (net (code "76") (name "unconnected-(P3-Pad19)") (class "Default")
      (node (ref "P3") (pin "19") (pinfunction "19_19") (pintype "passive"))
    )
    (net (code "77") (name "unconnected-(P3-Pad20)") (class "Default")
      (node (ref "P3") (pin "20") (pinfunction "20_20") (pintype "passive"))
    )
    (net (code "78") (name "unconnected-(P3-Pad21)") (class "Default")
      (node (ref "P3") (pin "21") (pinfunction "21_21") (pintype "passive"))
    )
    (net (code "79") (name "unconnected-(P3-Pad22)") (class "Default")
      (node (ref "P3") (pin "22") (pinfunction "22_22") (pintype "passive"))
    )
    (net (code "80") (name "unconnected-(P3-Pad23)") (class "Default")
      (node (ref "P3") (pin "23") (pinfunction "23_23") (pintype "passive"))
    )
    (net (code "81") (name "unconnected-(P3-Pad24)") (class "Default")
      (node (ref "P3") (pin "24") (pinfunction "24_24") (pintype "passive"))
    )
    (net (code "82") (name "unconnected-(P3-Pad25)") (class "Default")
      (node (ref "P3") (pin "25") (pinfunction "25_25") (pintype "passive"))
    )
    (net (code "83") (name "unconnected-(P3-Pad26)") (class "Default")
      (node (ref "P3") (pin "26") (pinfunction "26_26") (pintype "passive"))
    )
    (net (code "84") (name "unconnected-(P3-Pad27)") (class "Default")
      (node (ref "P3") (pin "27") (pinfunction "27_27") (pintype "passive"))
    )
    (net (code "85") (name "unconnected-(P3-Pad28)") (class "Default")
      (node (ref "P3") (pin "28") (pinfunction "28_28") (pintype "passive"))
    )
    (net (code "86") (name "unconnected-(P3-Pad29)") (class "Default")
      (node (ref "P3") (pin "29") (pinfunction "29_29") (pintype "passive"))
    )
    (net (code "87") (name "unconnected-(P3-Pad30)") (class "Default")
      (node (ref "P3") (pin "30") (pinfunction "30_30") (pintype "passive"))
    )
    (net (code "88") (name "unconnected-(P3-Pad31)") (class "Default")
      (node (ref "P3") (pin "31") (pinfunction "31_31") (pintype "passive"))
    )
    (net (code "89") (name "unconnected-(P3-Pad32)") (class "Default")
      (node (ref "P3") (pin "32") (pinfunction "32_32") (pintype "passive"))
    )
    (net (code "90") (name "unconnected-(P3-Pad33)") (class "Default")
      (node (ref "P3") (pin "33") (pinfunction "33_33") (pintype "passive"))
    )
    (net (code "91") (name "unconnected-(P3-Pad34)") (class "Default")
      (node (ref "P3") (pin "34") (pinfunction "34_34") (pintype "passive"))
    )
    (net (code "92") (name "unconnected-(P3-Pad35)") (class "Default")
      (node (ref "P3") (pin "35") (pinfunction "35_35") (pintype "passive"))
    )
    (net (code "93") (name "unconnected-(P3-Pad36)") (class "Default")
      (node (ref "P3") (pin "36") (pinfunction "36_36") (pintype "passive"))
    )
    (net (code "94") (name "unconnected-(P3-Pad37)") (class "Default")
      (node (ref "P3") (pin "37") (pinfunction "37_37") (pintype "passive"))
    )
    (net (code "95") (name "unconnected-(P3-Pad38)") (class "Default")
      (node (ref "P3") (pin "38") (pinfunction "38_38") (pintype "passive"))
    )
    (net (code "96") (name "unconnected-(U1-NC-Pad12)") (class "Default")
      (node (ref "U1") (pin "12") (pinfunction "NC_12") (pintype "passive"))
    )
    (net (code "97") (name "unconnected-(U3A-PA0-WKUP(PA0)-Pad14)") (class "Default")
      (node (ref "U3") (pin "14") (pinfunction "PA0-WKUP(PA0)_14") (pintype "bidirectional"))
    )
    (net (code "98") (name "unconnected-(U3A-PA1-Pad15)") (class "Default")
      (node (ref "U3") (pin "15") (pinfunction "PA1_15") (pintype "bidirectional"))
    )
    (net (code "99") (name "unconnected-(U3A-PA2-Pad16)") (class "Default")
      (node (ref "U3") (pin "16") (pinfunction "PA2_16") (pintype "bidirectional"))
    )
    (net (code "100") (name "unconnected-(U3A-PA3-Pad17)") (class "Default")
      (node (ref "U3") (pin "17") (pinfunction "PA3_17") (pintype "bidirectional"))
    )
    (net (code "101") (name "unconnected-(U3A-PA4-Pad20)") (class "Default")
      (node (ref "U3") (pin "20") (pinfunction "PA4_20") (pintype "bidirectional"))
    )
    (net (code "102") (name "unconnected-(U3A-PA5-Pad21)") (class "Default")
      (node (ref "U3") (pin "21") (pinfunction "PA5_21") (pintype "bidirectional"))
    )
    (net (code "103") (name "unconnected-(U3A-PA6-Pad22)") (class "Default")
      (node (ref "U3") (pin "22") (pinfunction "PA6_22") (pintype "bidirectional"))
    )
    (net (code "104") (name "unconnected-(U3A-PA7-Pad23)") (class "Default")
      (node (ref "U3") (pin "23") (pinfunction "PA7_23") (pintype "bidirectional"))
    )
    (net (code "105") (name "unconnected-(U3A-PA8-Pad41)") (class "Default")
      (node (ref "U3") (pin "41") (pinfunction "PA8_41") (pintype "bidirectional"))
    )
    (net (code "106") (name "unconnected-(U3A-PA9-Pad42)") (class "Default")
      (node (ref "U3") (pin "42") (pinfunction "PA9_42") (pintype "bidirectional"))
    )
    (net (code "107") (name "unconnected-(U3A-PA11-Pad44)") (class "Default")
      (node (ref "U3") (pin "44") (pinfunction "PA11_44") (pintype "bidirectional"))
    )
    (net (code "108") (name "unconnected-(U3A-PA12-Pad45)") (class "Default")
      (node (ref "U3") (pin "45") (pinfunction "PA12_45") (pintype "bidirectional"))
    )
    (net (code "109") (name "unconnected-(U3A-PA15(JTDI)-Pad50)") (class "Default")
      (node (ref "U3") (pin "50") (pinfunction "PA15(JTDI)_50") (pintype "bidirectional"))
    )
    (net (code "110") (name "unconnected-(U3A-PB0-Pad26)") (class "Default")
      (node (ref "U3") (pin "26") (pinfunction "PB0_26") (pintype "bidirectional"))
    )
    (net (code "111") (name "unconnected-(U3A-PB1-Pad27)") (class "Default")
      (node (ref "U3") (pin "27") (pinfunction "PB1_27") (pintype "bidirectional"))
    )
    (net (code "112") (name "unconnected-(U3A-PB3(JTDO{slash}TRACESWO)-Pad55)") (class "Default")
      (node (ref "U3") (pin "55") (pinfunction "PB3(JTDO/TRACESWO)_55") (pintype "bidirectional"))
    )
    (net (code "113") (name "unconnected-(U3A-PB4(NJTRST)-Pad56)") (class "Default")
      (node (ref "U3") (pin "56") (pinfunction "PB4(NJTRST)_56") (pintype "bidirectional"))
    )
    (net (code "114") (name "unconnected-(U3A-PB5-Pad57)") (class "Default")
      (node (ref "U3") (pin "57") (pinfunction "PB5_57") (pintype "bidirectional"))
    )
    (net (code "115") (name "unconnected-(U3A-PB6-Pad58)") (class "Default")
      (node (ref "U3") (pin "58") (pinfunction "PB6_58") (pintype "bidirectional"))
    )
    (net (code "116") (name "unconnected-(U3A-PB7-Pad59)") (class "Default")
      (node (ref "U3") (pin "59") (pinfunction "PB7_59") (pintype "bidirectional"))
    )
    (net (code "117") (name "unconnected-(U3A-PB8-Pad61)") (class "Default")
      (node (ref "U3") (pin "61") (pinfunction "PB8_61") (pintype "bidirectional"))
    )
    (net (code "118") (name "unconnected-(U3A-PB9-Pad62)") (class "Default")
      (node (ref "U3") (pin "62") (pinfunction "PB9_62") (pintype "bidirectional"))
    )
    (net (code "119") (name "unconnected-(U3A-PB12-Pad33)") (class "Default")
      (node (ref "U3") (pin "33") (pinfunction "PB12_33") (pintype "bidirectional"))
    )
    (net (code "120") (name "unconnected-(U3A-PB13-Pad34)") (class "Default")
      (node (ref "U3") (pin "34") (pinfunction "PB13_34") (pintype "bidirectional"))
    )
    (net (code "121") (name "unconnected-(U3A-PB14-Pad35)") (class "Default")
      (node (ref "U3") (pin "35") (pinfunction "PB14_35") (pintype "bidirectional"))
    )
    (net (code "122") (name "unconnected-(U3A-PB15-Pad36)") (class "Default")
      (node (ref "U3") (pin "36") (pinfunction "PB15_36") (pintype "bidirectional"))
    )
    (net (code "123") (name "unconnected-(U3A-PC0-Pad8)") (class "Default")
      (node (ref "U3") (pin "8") (pinfunction "PC0_8") (pintype "bidirectional"))
    )
    (net (code "124") (name "unconnected-(U3A-PC1-Pad9)") (class "Default")
      (node (ref "U3") (pin "9") (pinfunction "PC1_9") (pintype "bidirectional"))
    )
    (net (code "125") (name "unconnected-(U3A-PC2-Pad10)") (class "Default")
      (node (ref "U3") (pin "10") (pinfunction "PC2_10") (pintype "bidirectional"))
    )
    (net (code "126") (name "unconnected-(U3A-PC3-Pad11)") (class "Default")
      (node (ref "U3") (pin "11") (pinfunction "PC3_11") (pintype "bidirectional"))
    )
    (net (code "127") (name "unconnected-(U3A-PC4-Pad24)") (class "Default")
      (node (ref "U3") (pin "24") (pinfunction "PC4_24") (pintype "bidirectional"))
    )
    (net (code "128") (name "unconnected-(U3A-PC5-Pad25)") (class "Default")
      (node (ref "U3") (pin "25") (pinfunction "PC5_25") (pintype "bidirectional"))
    )
    (net (code "129") (name "unconnected-(U3A-PC6-Pad37)") (class "Default")
      (node (ref "U3") (pin "37") (pinfunction "PC6_37") (pintype "bidirectional"))
    )
    (net (code "130") (name "unconnected-(U3A-PC7-Pad38)") (class "Default")
      (node (ref "U3") (pin "38") (pinfunction "PC7_38") (pintype "bidirectional"))
    )
    (net (code "131") (name "unconnected-(U3A-PC8-Pad39)") (class "Default")
      (node (ref "U3") (pin "39") (pinfunction "PC8_39") (pintype "bidirectional"))
    )
    (net (code "132") (name "unconnected-(U3A-PC9-Pad40)") (class "Default")
      (node (ref "U3") (pin "40") (pinfunction "PC9_40") (pintype "bidirectional"))
    )
    (net (code "133") (name "unconnected-(U3A-PC10-Pad51)") (class "Default")
      (node (ref "U3") (pin "51") (pinfunction "PC10_51") (pintype "bidirectional"))
    )
    (net (code "134") (name "unconnected-(U3A-PC11-Pad52)") (class "Default")
      (node (ref "U3") (pin "52") (pinfunction "PC11_52") (pintype "bidirectional"))
    )
    (net (code "135") (name "unconnected-(U3A-PC12-Pad53)") (class "Default")
      (node (ref "U3") (pin "53") (pinfunction "PC12_53") (pintype "bidirectional"))
    )
    (net (code "136") (name "unconnected-(U3A-PC13-Pad2)") (class "Default")
      (node (ref "U3") (pin "2") (pinfunction "PC13_2") (pintype "bidirectional"))
    )
    (net (code "137") (name "unconnected-(U3A-PD2-Pad54)") (class "Default")
      (node (ref "U3") (pin "54") (pinfunction "PD2_54") (pintype "bidirectional"))
    )
  )
)
